# USER_IO.net
KiCad netlist of a schematic drawn in Altium Designer
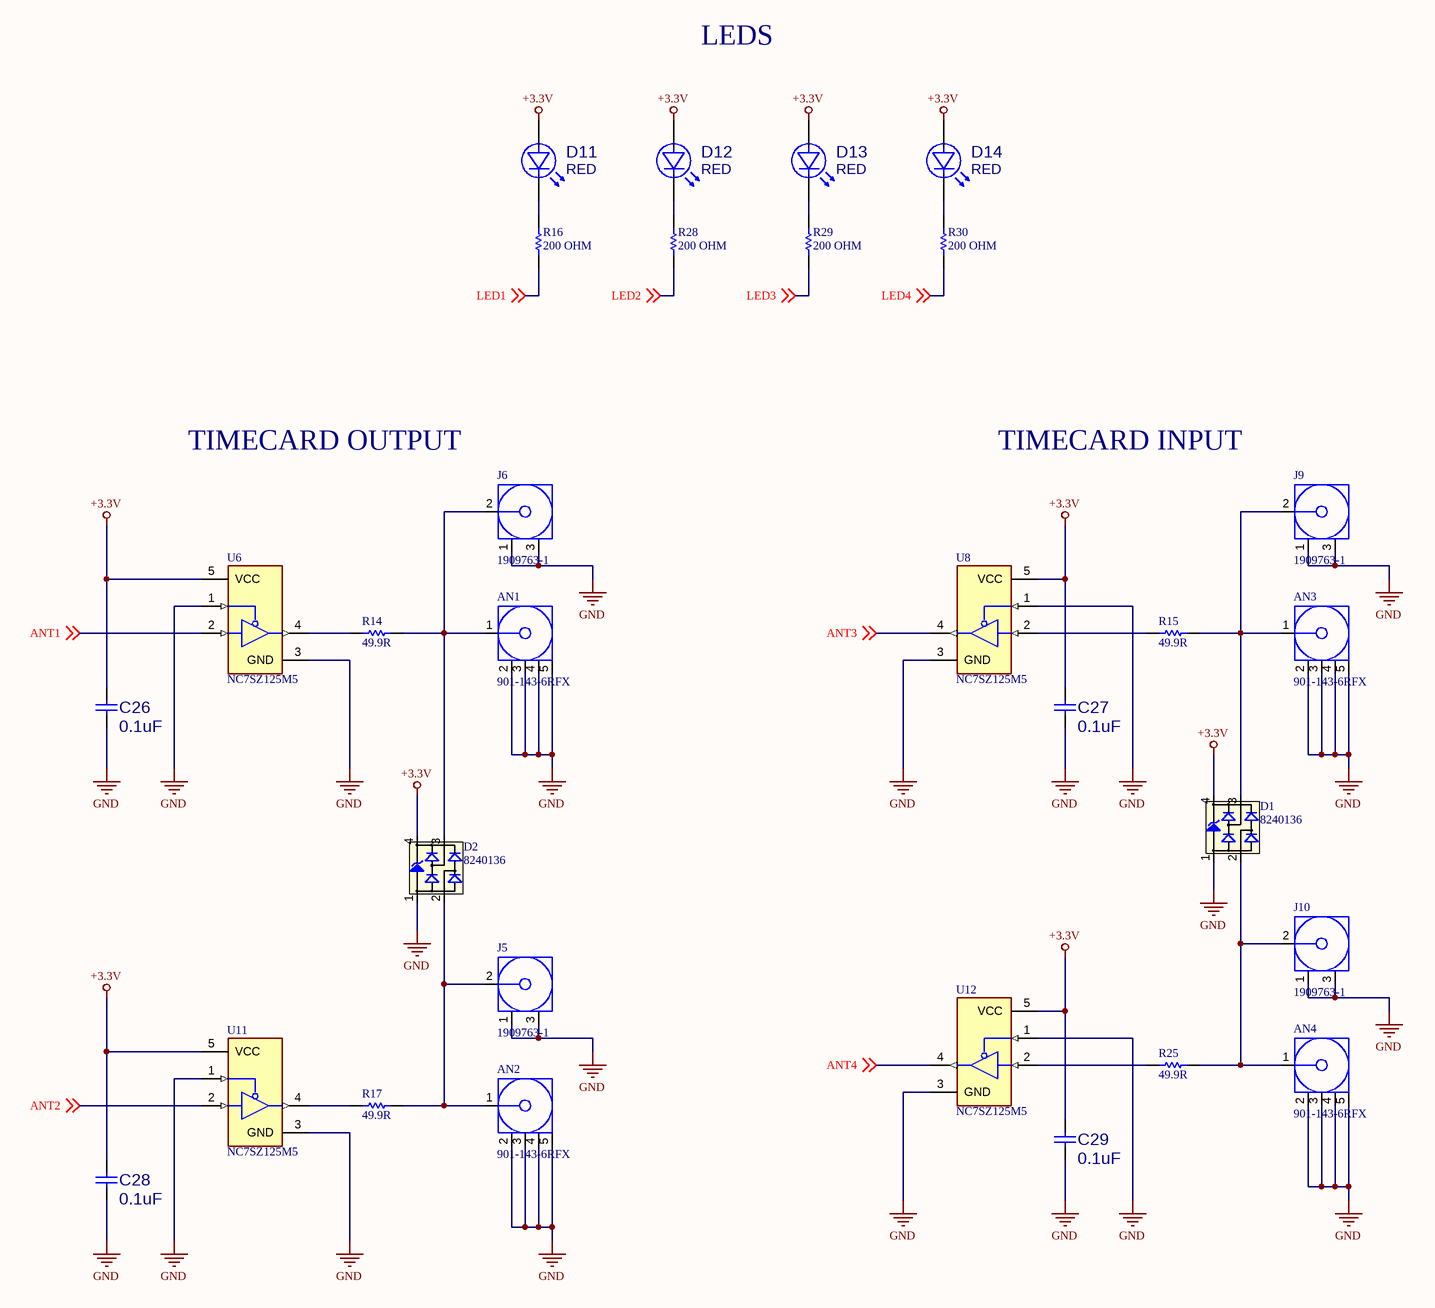
[diagram p0: USER_IO.SchDoc]

(export (version "E")
  (design (tool "Eeschema 10.0.6"))
  (components
    (comp (ref "AN1")
      (value "901-143-6RFX")
      (footprint "AMPH-901-143-6RFX_V")
      (description "Coaxial connector, 50 Ohm, -65 to 165 degC, 5-Pin THD, RoHS, Bulk")
      (fields (field (name "MANUFACTURER") "Amphenol"))
      (libsource (lib "Altium Content Vault") (part "CN-S-4F-RF5"))
    )
    (comp (ref "AN2")
      (value "901-143-6RFX")
      (footprint "AMPH-901-143-6RFX_V")
      (description "Coaxial connector, 50 Ohm, -65 to 165 degC, 5-Pin THD, RoHS, Bulk")
      (fields (field (name "MANUFACTURER") "Amphenol"))
      (libsource (lib "Altium Content Vault") (part "CN-S-4F-RF5"))
    )
    (comp (ref "AN3")
      (value "901-143-6RFX")
      (footprint "AMPH-901-143-6RFX_V")
      (description "Coaxial connector, 50 Ohm, -65 to 165 degC, 5-Pin THD, RoHS, Bulk")
      (fields (field (name "MANUFACTURER") "Amphenol"))
      (libsource (lib "Altium Content Vault") (part "CN-S-4F-RF5"))
    )
    (comp (ref "AN4")
      (value "901-143-6RFX")
      (footprint "AMPH-901-143-6RFX_V")
      (description "Coaxial connector, 50 Ohm, -65 to 165 degC, 5-Pin THD, RoHS, Bulk")
      (fields (field (name "MANUFACTURER") "Amphenol"))
      (libsource (lib "Altium Content Vault") (part "CN-S-4F-RF5"))
    )
    (comp (ref "C26")
      (value "0.1uF")
      (footprint "CAPC1608X87X45ML20T05")
      (description "C0603X104K5RACAUTO")
      (fields (field (name "MANUFACTURER") "Kemet"))
      (libsource (lib "Altium Content Vault") (part "CAP"))
    )
    (comp (ref "C27")
      (value "0.1uF")
      (footprint "CAPC1608X87X45ML20T05")
      (description "C0603X104K5RACAUTO")
      (fields (field (name "MANUFACTURER") "Kemet"))
      (libsource (lib "Altium Content Vault") (part "CAP"))
    )
    (comp (ref "C28")
      (value "0.1uF")
      (footprint "CAPC1608X87X45ML20T05")
      (description "C0603X104K5RACAUTO")
      (fields (field (name "MANUFACTURER") "Kemet"))
      (libsource (lib "Altium Content Vault") (part "CAP"))
    )
    (comp (ref "C29")
      (value "0.1uF")
      (footprint "CAPC1608X87X45ML20T05")
      (description "C0603X104K5RACAUTO")
      (fields (field (name "MANUFACTURER") "Kemet"))
      (libsource (lib "Altium Content Vault") (part "CAP"))
    )
    (comp (ref "D1")
      (value "8240136")
      (footprint "SOT143-4L")
      (description "TVS Diode WE-TVS-HS, VRWM=3.3V")
      (fields (field (name "MANUFACTURER") "Wuerth Elektronik"))
      (libsource (lib "Altium Content Vault") (part "WE-TVS-HS-4"))
    )
    (comp (ref "D2")
      (value "8240136")
      (footprint "SOT143-4L")
      (description "TVS Diode WE-TVS-HS, VRWM=3.3V")
      (fields (field (name "MANUFACTURER") "Wuerth Elektronik"))
      (libsource (lib "Altium Content Vault") (part "WE-TVS-HS-4"))
    )
    (comp (ref "D11")
      (value "RED")
      (footprint "DIOM1608X06N")
      (description "LED, RED, SML-LX0603, 635NM, 2V, 20MA, 0603")
      (fields
        (field (name "MFG PART NUM") "SML-LX0603IW-TR")
        (field (name "VALENTIUM PART NUM") "<VALENTIUM>")
      )
      (libsource (lib "Passives") (part "SMTLED_RED_0603_SML"))
    )
    (comp (ref "D12")
      (value "RED")
      (footprint "DIOM1608X06N")
      (description "LED, RED, SML-LX0603, 635NM, 2V, 20MA, 0603")
      (fields
        (field (name "MFG PART NUM") "SML-LX0603IW-TR")
        (field (name "VALENTIUM PART NUM") "<VALENTIUM>")
      )
      (libsource (lib "Passives") (part "SMTLED_RED_0603_SML"))
    )
    (comp (ref "D13")
      (value "RED")
      (footprint "DIOM1608X06N")
      (description "LED, RED, SML-LX0603, 635NM, 2V, 20MA, 0603")
      (fields
        (field (name "MFG PART NUM") "SML-LX0603IW-TR")
        (field (name "VALENTIUM PART NUM") "<VALENTIUM>")
      )
      (libsource (lib "Passives") (part "SMTLED_RED_0603_SML"))
    )
    (comp (ref "D14")
      (value "RED")
      (footprint "DIOM1608X06N")
      (description "LED, RED, SML-LX0603, 635NM, 2V, 20MA, 0603")
      (fields
        (field (name "MFG PART NUM") "SML-LX0603IW-TR")
        (field (name "VALENTIUM PART NUM") "<VALENTIUM>")
      )
      (libsource (lib "Passives") (part "SMTLED_RED_0603_SML"))
    )
    (comp (ref "J5")
      (value "1909763-1")
      (footprint "TECO-1909763-1_V")
      (description "Ultra Miniature Coaxial Connector Jack, 60 V, 50 Ohm, -40 to 90 degC, RoHS, Tape and Reel")
      (fields (field (name "MANUFACTURER") "TE Connectivity"))
      (libsource (lib "Altium Content Vault") (part "CN-1P-M-RF3"))
    )
    (comp (ref "J6")
      (value "1909763-1")
      (footprint "TECO-1909763-1_V")
      (description "Ultra Miniature Coaxial Connector Jack, 60 V, 50 Ohm, -40 to 90 degC, RoHS, Tape and Reel")
      (fields (field (name "MANUFACTURER") "TE Connectivity"))
      (libsource (lib "Altium Content Vault") (part "CN-1P-M-RF3"))
    )
    (comp (ref "J9")
      (value "1909763-1")
      (footprint "TECO-1909763-1_V")
      (description "Ultra Miniature Coaxial Connector Jack, 60 V, 50 Ohm, -40 to 90 degC, RoHS, Tape and Reel")
      (fields (field (name "MANUFACTURER") "TE Connectivity"))
      (libsource (lib "Altium Content Vault") (part "CN-1P-M-RF3"))
    )
    (comp (ref "J10")
      (value "1909763-1")
      (footprint "TECO-1909763-1_V")
      (description "Ultra Miniature Coaxial Connector Jack, 60 V, 50 Ohm, -40 to 90 degC, RoHS, Tape and Reel")
      (fields (field (name "MANUFACTURER") "TE Connectivity"))
      (libsource (lib "Altium Content Vault") (part "CN-1P-M-RF3"))
    )
    (comp (ref "R14")
      (value "49.9R")
      (footprint "RESC1608X55X25NL10T15")
      (libsource (lib "Altium Content Vault") (part "RES-2"))
    )
    (comp (ref "R15")
      (value "49.9R")
      (footprint "RESC1608X55X25NL10T15")
      (libsource (lib "Altium Content Vault") (part "RES-2"))
    )
    (comp (ref "R16")
      (value "200 OHM")
      (footprint "RESC1608X55X30NL15T15")
      (description "ERJ-3EKF2000V")
      (fields (field (name "MANUFACTURER") "Panasonic"))
      (libsource (lib "Altium Content Vault") (part "RES"))
    )
    (comp (ref "R17")
      (value "49.9R")
      (footprint "RESC1608X55X25NL10T15")
      (libsource (lib "Altium Content Vault") (part "RES-2"))
    )
    (comp (ref "R25")
      (value "49.9R")
      (footprint "RESC1608X55X25NL10T15")
      (libsource (lib "Altium Content Vault") (part "RES-2"))
    )
    (comp (ref "R28")
      (value "200 OHM")
      (footprint "RESC1608X55X30NL15T15")
      (description "ERJ-3EKF2000V")
      (fields (field (name "MANUFACTURER") "Panasonic"))
      (libsource (lib "Altium Content Vault") (part "RES"))
    )
    (comp (ref "R29")
      (value "200 OHM")
      (footprint "RESC1608X55X30NL15T15")
      (description "ERJ-3EKF2000V")
      (fields (field (name "MANUFACTURER") "Panasonic"))
      (libsource (lib "Altium Content Vault") (part "RES"))
    )
    (comp (ref "R30")
      (value "200 OHM")
      (footprint "RESC1608X55X30NL15T15")
      (description "ERJ-3EKF2000V")
      (fields (field (name "MANUFACTURER") "Panasonic"))
      (libsource (lib "Altium Content Vault") (part "RES"))
    )
    (comp (ref "U6")
      (value "NC7SZ125M5")
      (footprint "FP-318BQ-MFG")
      (description "IC BUF NON-INVERT 5.5V SOT23-5")
      (fields
        (field (name "MANUFACTURER") "ON Semiconductor")
        (field (name "OCTOPART") "https://octopart.com/nc7sz125m5-on+semiconductor-84330746")
      )
      (libsource (lib "") (part "3620477901728614f2110f3aa036e68_1"))
    )
    (comp (ref "U8")
      (value "NC7SZ125M5")
      (footprint "FP-318BQ-MFG")
      (description "IC BUF NON-INVERT 5.5V SOT23-5")
      (fields
        (field (name "MANUFACTURER") "ON Semiconductor")
        (field (name "OCTOPART") "https://octopart.com/nc7sz125m5-on+semiconductor-84330746")
      )
      (libsource (lib "Altium Content Vault") (part "3620477901728614f2110f3aa036e68"))
    )
    (comp (ref "U11")
      (value "NC7SZ125M5")
      (footprint "FP-318BQ-MFG")
      (description "IC BUF NON-INVERT 5.5V SOT23-5")
      (fields
        (field (name "MANUFACTURER") "ON Semiconductor")
        (field (name "OCTOPART") "https://octopart.com/nc7sz125m5-on+semiconductor-84330746")
      )
      (libsource (lib "") (part "3620477901728614f2110f3aa036e68_1"))
    )
    (comp (ref "U12")
      (value "NC7SZ125M5")
      (footprint "FP-318BQ-MFG")
      (description "IC BUF NON-INVERT 5.5V SOT23-5")
      (fields
        (field (name "MANUFACTURER") "ON Semiconductor")
        (field (name "OCTOPART") "https://octopart.com/nc7sz125m5-on+semiconductor-84330746")
      )
      (libsource (lib "Altium Content Vault") (part "3620477901728614f2110f3aa036e68"))
    )
  )
  (nets
    (net (code "1") (name "+3.3V") (class "Default")
      (node (ref "C26") (pin "1") (pinfunction "1_1") (pintype "passive"))
      (node (ref "C27") (pin "1") (pinfunction "1_1") (pintype "passive"))
      (node (ref "C28") (pin "1") (pinfunction "1_1") (pintype "passive"))
      (node (ref "C29") (pin "1") (pinfunction "1_1") (pintype "passive"))
      (node (ref "D1") (pin "4") (pinfunction "VDD_4") (pintype "passive"))
      (node (ref "D11") (pin "2") (pinfunction "A_2") (pintype "passive"))
      (node (ref "D12") (pin "2") (pinfunction "A_2") (pintype "passive"))
      (node (ref "D13") (pin "2") (pinfunction "A_2") (pintype "passive"))
      (node (ref "D14") (pin "2") (pinfunction "A_2") (pintype "passive"))
      (node (ref "D2") (pin "4") (pinfunction "VDD_4") (pintype "passive"))
      (node (ref "U11") (pin "5") (pinfunction "VCC_5") (pintype "power_in"))
      (node (ref "U12") (pin "5") (pinfunction "VCC_5") (pintype "power_in"))
      (node (ref "U6") (pin "5") (pinfunction "VCC_5") (pintype "power_in"))
      (node (ref "U8") (pin "5") (pinfunction "VCC_5") (pintype "power_in"))
    )
    (net (code "2") (name "ANT1") (class "Default")
      (node (ref "U6") (pin "2") (pinfunction "A_2") (pintype "input"))
    )
    (net (code "3") (name "ANT2") (class "Default")
      (node (ref "U11") (pin "2") (pinfunction "A_2") (pintype "input"))
    )
    (net (code "4") (name "ANT3") (class "Default")
      (node (ref "U8") (pin "4") (pinfunction "Y_4") (pintype "output"))
    )
    (net (code "5") (name "ANT4") (class "Default")
      (node (ref "U12") (pin "4") (pinfunction "Y_4") (pintype "output"))
    )
    (net (code "6") (name "GND") (class "Default")
      (node (ref "AN1") (pin "2") (pinfunction "2_2") (pintype "passive"))
      (node (ref "AN1") (pin "3") (pinfunction "3_3") (pintype "passive"))
      (node (ref "AN1") (pin "4") (pinfunction "4_4") (pintype "passive"))
      (node (ref "AN1") (pin "5") (pinfunction "5_5") (pintype "passive"))
      (node (ref "AN2") (pin "2") (pinfunction "2_2") (pintype "passive"))
      (node (ref "AN2") (pin "3") (pinfunction "3_3") (pintype "passive"))
      (node (ref "AN2") (pin "4") (pinfunction "4_4") (pintype "passive"))
      (node (ref "AN2") (pin "5") (pinfunction "5_5") (pintype "passive"))
      (node (ref "AN3") (pin "2") (pinfunction "2_2") (pintype "passive"))
      (node (ref "AN3") (pin "3") (pinfunction "3_3") (pintype "passive"))
      (node (ref "AN3") (pin "4") (pinfunction "4_4") (pintype "passive"))
      (node (ref "AN3") (pin "5") (pinfunction "5_5") (pintype "passive"))
      (node (ref "AN4") (pin "2") (pinfunction "2_2") (pintype "passive"))
      (node (ref "AN4") (pin "3") (pinfunction "3_3") (pintype "passive"))
      (node (ref "AN4") (pin "4") (pinfunction "4_4") (pintype "passive"))
      (node (ref "AN4") (pin "5") (pinfunction "5_5") (pintype "passive"))
      (node (ref "C26") (pin "2") (pinfunction "2_2") (pintype "passive"))
      (node (ref "C27") (pin "2") (pinfunction "2_2") (pintype "passive"))
      (node (ref "C28") (pin "2") (pinfunction "2_2") (pintype "passive"))
      (node (ref "C29") (pin "2") (pinfunction "2_2") (pintype "passive"))
      (node (ref "D1") (pin "1") (pinfunction "GND_1") (pintype "passive"))
      (node (ref "D2") (pin "1") (pinfunction "GND_1") (pintype "passive"))
      (node (ref "J10") (pin "1") (pinfunction "1_1") (pintype "passive"))
      (node (ref "J10") (pin "3") (pinfunction "3_3") (pintype "passive"))
      (node (ref "J5") (pin "1") (pinfunction "1_1") (pintype "passive"))
      (node (ref "J5") (pin "3") (pinfunction "3_3") (pintype "passive"))
      (node (ref "J6") (pin "1") (pinfunction "1_1") (pintype "passive"))
      (node (ref "J6") (pin "3") (pinfunction "3_3") (pintype "passive"))
      (node (ref "J9") (pin "1") (pinfunction "1_1") (pintype "passive"))
      (node (ref "J9") (pin "3") (pinfunction "3_3") (pintype "passive"))
      (node (ref "U11") (pin "1") (pinfunction "~{OE}_1") (pintype "input"))
      (node (ref "U11") (pin "3") (pinfunction "GND_3") (pintype "power_in"))
      (node (ref "U12") (pin "1") (pinfunction "~{OE}_1") (pintype "input"))
      (node (ref "U12") (pin "3") (pinfunction "GND_3") (pintype "power_in"))
      (node (ref "U6") (pin "1") (pinfunction "~{OE}_1") (pintype "input"))
      (node (ref "U6") (pin "3") (pinfunction "GND_3") (pintype "power_in"))
      (node (ref "U8") (pin "1") (pinfunction "~{OE}_1") (pintype "input"))
      (node (ref "U8") (pin "3") (pinfunction "GND_3") (pintype "power_in"))
    )
    (net (code "7") (name "LED1") (class "Default")
      (node (ref "R16") (pin "1") (pinfunction "1_1") (pintype "passive"))
    )
    (net (code "8") (name "LED2") (class "Default")
      (node (ref "R28") (pin "1") (pinfunction "1_1") (pintype "passive"))
    )
    (net (code "9") (name "LED3") (class "Default")
      (node (ref "R29") (pin "1") (pinfunction "1_1") (pintype "passive"))
    )
    (net (code "10") (name "LED4") (class "Default")
      (node (ref "R30") (pin "1") (pinfunction "1_1") (pintype "passive"))
    )
    (net (code "11") (name "Net-(D1-I{slash}O1)") (class "Default")
      (node (ref "AN4") (pin "1") (pinfunction "1_1") (pintype "passive"))
      (node (ref "D1") (pin "2") (pinfunction "I/O1_2") (pintype "passive"))
      (node (ref "J10") (pin "2") (pinfunction "2_2") (pintype "passive"))
      (node (ref "R25") (pin "2") (pinfunction "2_2") (pintype "passive"))
    )
    (net (code "12") (name "Net-(D1-I{slash}O2)") (class "Default")
      (node (ref "AN3") (pin "1") (pinfunction "1_1") (pintype "passive"))
      (node (ref "D1") (pin "3") (pinfunction "I/O2_3") (pintype "passive"))
      (node (ref "J9") (pin "2") (pinfunction "2_2") (pintype "passive"))
      (node (ref "R15") (pin "2") (pinfunction "2_2") (pintype "passive"))
    )
    (net (code "13") (name "Net-(D2-I{slash}O1)") (class "Default")
      (node (ref "AN2") (pin "1") (pinfunction "1_1") (pintype "passive"))
      (node (ref "D2") (pin "2") (pinfunction "I/O1_2") (pintype "passive"))
      (node (ref "J5") (pin "2") (pinfunction "2_2") (pintype "passive"))
      (node (ref "R17") (pin "2") (pinfunction "2_2") (pintype "passive"))
    )
    (net (code "14") (name "Net-(D2-I{slash}O2)") (class "Default")
      (node (ref "AN1") (pin "1") (pinfunction "1_1") (pintype "passive"))
      (node (ref "D2") (pin "3") (pinfunction "I/O2_3") (pintype "passive"))
      (node (ref "J6") (pin "2") (pinfunction "2_2") (pintype "passive"))
      (node (ref "R14") (pin "2") (pinfunction "2_2") (pintype "passive"))
    )
    (net (code "15") (name "Net-(D11-K)") (class "Default")
      (node (ref "D11") (pin "1") (pinfunction "K_1") (pintype "passive"))
      (node (ref "R16") (pin "2") (pinfunction "2_2") (pintype "passive"))
    )
    (net (code "16") (name "Net-(D12-K)") (class "Default")
      (node (ref "D12") (pin "1") (pinfunction "K_1") (pintype "passive"))
      (node (ref "R28") (pin "2") (pinfunction "2_2") (pintype "passive"))
    )
    (net (code "17") (name "Net-(D13-K)") (class "Default")
      (node (ref "D13") (pin "1") (pinfunction "K_1") (pintype "passive"))
      (node (ref "R29") (pin "2") (pinfunction "2_2") (pintype "passive"))
    )
    (net (code "18") (name "Net-(D14-K)") (class "Default")
      (node (ref "D14") (pin "1") (pinfunction "K_1") (pintype "passive"))
      (node (ref "R30") (pin "2") (pinfunction "2_2") (pintype "passive"))
    )
    (net (code "19") (name "Net-(U6-Y)") (class "Default")
      (node (ref "R14") (pin "1") (pinfunction "1_1") (pintype "passive"))
      (node (ref "U6") (pin "4") (pinfunction "Y_4") (pintype "output"))
    )
    (net (code "20") (name "Net-(U8-A)") (class "Default")
      (node (ref "R15") (pin "1") (pinfunction "1_1") (pintype "passive"))
      (node (ref "U8") (pin "2") (pinfunction "A_2") (pintype "input"))
    )
    (net (code "21") (name "Net-(U11-Y)") (class "Default")
      (node (ref "R17") (pin "1") (pinfunction "1_1") (pintype "passive"))
      (node (ref "U11") (pin "4") (pinfunction "Y_4") (pintype "output"))
    )
    (net (code "22") (name "Net-(U12-A)") (class "Default")
      (node (ref "R25") (pin "1") (pinfunction "1_1") (pintype "passive"))
      (node (ref "U12") (pin "2") (pinfunction "A_2") (pintype "input"))
    )
  )
)
